# smpsu.net
KiCad netlist of a schematic drawn in EAGLE
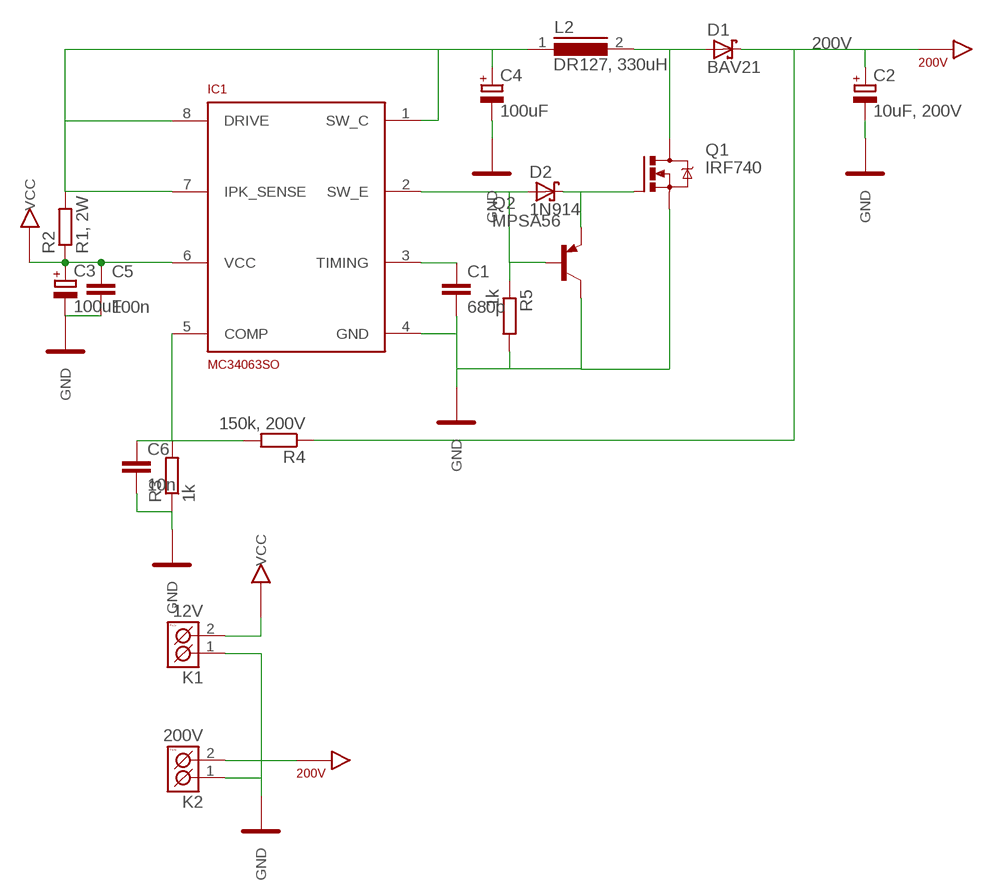
[diagram p0: schematic, sheet 1]

(export (version "E")
  (design (tool "Eeschema 10.0.6"))
  (components
    (comp (ref "C1")
      (value "680p")
      (footprint "eagle-import:C0805")
      (libsource (lib "eagle-import") (part "resistor_C-EUC0805"))
    )
    (comp (ref "C2")
      (value "10uF, 200V")
      (footprint "eagle-import:E3,5-10")
      (libsource (lib "eagle-import") (part "CPOL-EUE3.5-10"))
    )
    (comp (ref "C3")
      (value "100uF")
      (footprint "eagle-import:PANASONIC_D")
      (libsource (lib "eagle-import") (part "CPOL-EUD"))
    )
    (comp (ref "C4")
      (value "100uF")
      (footprint "eagle-import:PANASONIC_D")
      (libsource (lib "eagle-import") (part "CPOL-EUD"))
    )
    (comp (ref "C5")
      (value "100n")
      (footprint "eagle-import:C0805")
      (libsource (lib "eagle-import") (part "C-EUC0805"))
    )
    (comp (ref "C6")
      (value "10n")
      (footprint "eagle-import:C0805")
      (libsource (lib "eagle-import") (part "C-EUC0805"))
    )
    (comp (ref "D1")
      (value "BAV21")
      (footprint "eagle-import:DO35-7")
      (libsource (lib "eagle-import") (part "SCHOTTKY-DIODEDO35-7"))
    )
    (comp (ref "D2")
      (value "1N914")
      (footprint "eagle-import:DO35-7")
      (libsource (lib "eagle-import") (part "SCHOTTKY-DIODEDO35-7"))
    )
    (comp (ref "IC1")
      (value "MC34063SO")
      (footprint "eagle-import:SOP08")
      (libsource (lib "eagle-import") (part "MC34063SO"))
    )
    (comp (ref "K1")
      (value "12V")
      (footprint "eagle-import:ARK500_2")
      (libsource (lib "eagle-import") (part "ARK500/2"))
    )
    (comp (ref "K2")
      (value "200V")
      (footprint "eagle-import:ARK500_2")
      (libsource (lib "eagle-import") (part "ARK500/2"))
    )
    (comp (ref "L2")
      (value "DR127, 330uH")
      (footprint "eagle-import:DR127")
      (libsource (lib "eagle-import") (part "DR127"))
    )
    (comp (ref "Q1")
      (value "IRF740")
      (footprint "eagle-import:TO220BV")
      (libsource (lib "eagle-import") (part "IRF740"))
    )
    (comp (ref "Q2")
      (value "MPSA56")
      (footprint "eagle-import:TO92-CBE")
      (libsource (lib "eagle-import") (part "MPSA56"))
    )
    (comp (ref "R2")
      (value "R1, 2W")
      (footprint "eagle-import:V234_12")
      (libsource (lib "eagle-import") (part "R-EU_V234/12"))
    )
    (comp (ref "R3")
      (value "1k")
      (footprint "eagle-import:R0805")
      (libsource (lib "eagle-import") (part "R-EU_R0805"))
    )
    (comp (ref "R4")
      (value "150k, 200V")
      (footprint "eagle-import:R0805")
      (libsource (lib "eagle-import") (part "R-EU_R0805"))
    )
    (comp (ref "R5")
      (value "1k")
      (footprint "eagle-import:R0805")
      (libsource (lib "eagle-import") (part "R-EU_R0805"))
    )
  )
  (nets
    (net (code "1") (name "200V") (class "Default")
      (node (ref "C2") (pin "+") (pinfunction "+_+") (pintype "passive"))
      (node (ref "D1") (pin "C") (pinfunction "C_C") (pintype "passive"))
      (node (ref "K2") (pin "2") (pinfunction "K2_2") (pintype "passive"))
      (node (ref "R4") (pin "1") (pinfunction "1_1") (pintype "passive"))
    )
    (net (code "2") (name "GND") (class "Default")
      (node (ref "C1") (pin "2") (pinfunction "2_2") (pintype "passive"))
      (node (ref "C2") (pin "-") (pinfunction "-_-") (pintype "passive"))
      (node (ref "C3") (pin "-") (pinfunction "-_-") (pintype "passive"))
      (node (ref "C4") (pin "-") (pinfunction "-_-") (pintype "passive"))
      (node (ref "C5") (pin "2") (pinfunction "2_2") (pintype "passive"))
      (node (ref "C6") (pin "2") (pinfunction "2_2") (pintype "passive"))
      (node (ref "IC1") (pin "4") (pinfunction "GND_4") (pintype "bidirectional"))
      (node (ref "K1") (pin "1") (pinfunction "K1_1") (pintype "passive"))
      (node (ref "K2") (pin "1") (pinfunction "K1_1") (pintype "passive"))
      (node (ref "Q1") (pin "S") (pinfunction "S_S") (pintype "passive"))
      (node (ref "Q2") (pin "C") (pinfunction "C_C") (pintype "passive"))
      (node (ref "R3") (pin "1") (pinfunction "1_1") (pintype "passive"))
      (node (ref "R5") (pin "2") (pinfunction "2_2") (pintype "passive"))
    )
    (net (code "3") (name "Net-(D1-PadA)") (class "Default")
      (node (ref "D1") (pin "A") (pinfunction "A_A") (pintype "passive"))
      (node (ref "L2") (pin "2") (pinfunction "2_2") (pintype "passive"))
      (node (ref "Q1") (pin "D") (pinfunction "D_D") (pintype "passive"))
    )
    (net (code "4") (name "Net-(D2-PadC)") (class "Default")
      (node (ref "D2") (pin "C") (pinfunction "C_C") (pintype "passive"))
      (node (ref "Q1") (pin "G") (pinfunction "G_G") (pintype "passive"))
      (node (ref "Q2") (pin "E") (pinfunction "E_E") (pintype "passive"))
    )
    (net (code "5") (name "Net-(IC1-COMP)") (class "Default")
      (node (ref "C6") (pin "1") (pinfunction "1_1") (pintype "passive"))
      (node (ref "IC1") (pin "5") (pinfunction "COMP_5") (pintype "bidirectional"))
      (node (ref "R3") (pin "2") (pinfunction "2_2") (pintype "passive"))
      (node (ref "R4") (pin "2") (pinfunction "2_2") (pintype "passive"))
    )
    (net (code "6") (name "Net-(IC1-DRIVE)") (class "Default")
      (node (ref "C4") (pin "+") (pinfunction "+_+") (pintype "passive"))
      (node (ref "IC1") (pin "1") (pinfunction "SW_C_1") (pintype "bidirectional"))
      (node (ref "IC1") (pin "7") (pinfunction "IPK_SENSE_7") (pintype "bidirectional"))
      (node (ref "IC1") (pin "8") (pinfunction "DRIVE_8") (pintype "bidirectional"))
      (node (ref "L2") (pin "1") (pinfunction "1_1") (pintype "passive"))
      (node (ref "R2") (pin "2") (pinfunction "2_2") (pintype "passive"))
    )
    (net (code "7") (name "Net-(IC1-SW_E)") (class "Default")
      (node (ref "D2") (pin "A") (pinfunction "A_A") (pintype "passive"))
      (node (ref "IC1") (pin "2") (pinfunction "SW_E_2") (pintype "bidirectional"))
      (node (ref "Q2") (pin "B") (pinfunction "B_B") (pintype "passive"))
      (node (ref "R5") (pin "1") (pinfunction "1_1") (pintype "passive"))
    )
    (net (code "8") (name "Net-(IC1-TIMING)") (class "Default")
      (node (ref "C1") (pin "1") (pinfunction "1_1") (pintype "passive"))
      (node (ref "IC1") (pin "3") (pinfunction "TIMING_3") (pintype "bidirectional"))
    )
    (net (code "9") (name "VCC") (class "Default")
      (node (ref "C3") (pin "+") (pinfunction "+_+") (pintype "passive"))
      (node (ref "C5") (pin "1") (pinfunction "1_1") (pintype "passive"))
      (node (ref "IC1") (pin "6") (pinfunction "VCC_6") (pintype "bidirectional"))
      (node (ref "K1") (pin "2") (pinfunction "K2_2") (pintype "passive"))
      (node (ref "R2") (pin "1") (pinfunction "1_1") (pintype "passive"))
    )
  )
)
